# BoilerInterfaceV00.net
KiCad netlist of a schematic drawn in EAGLE
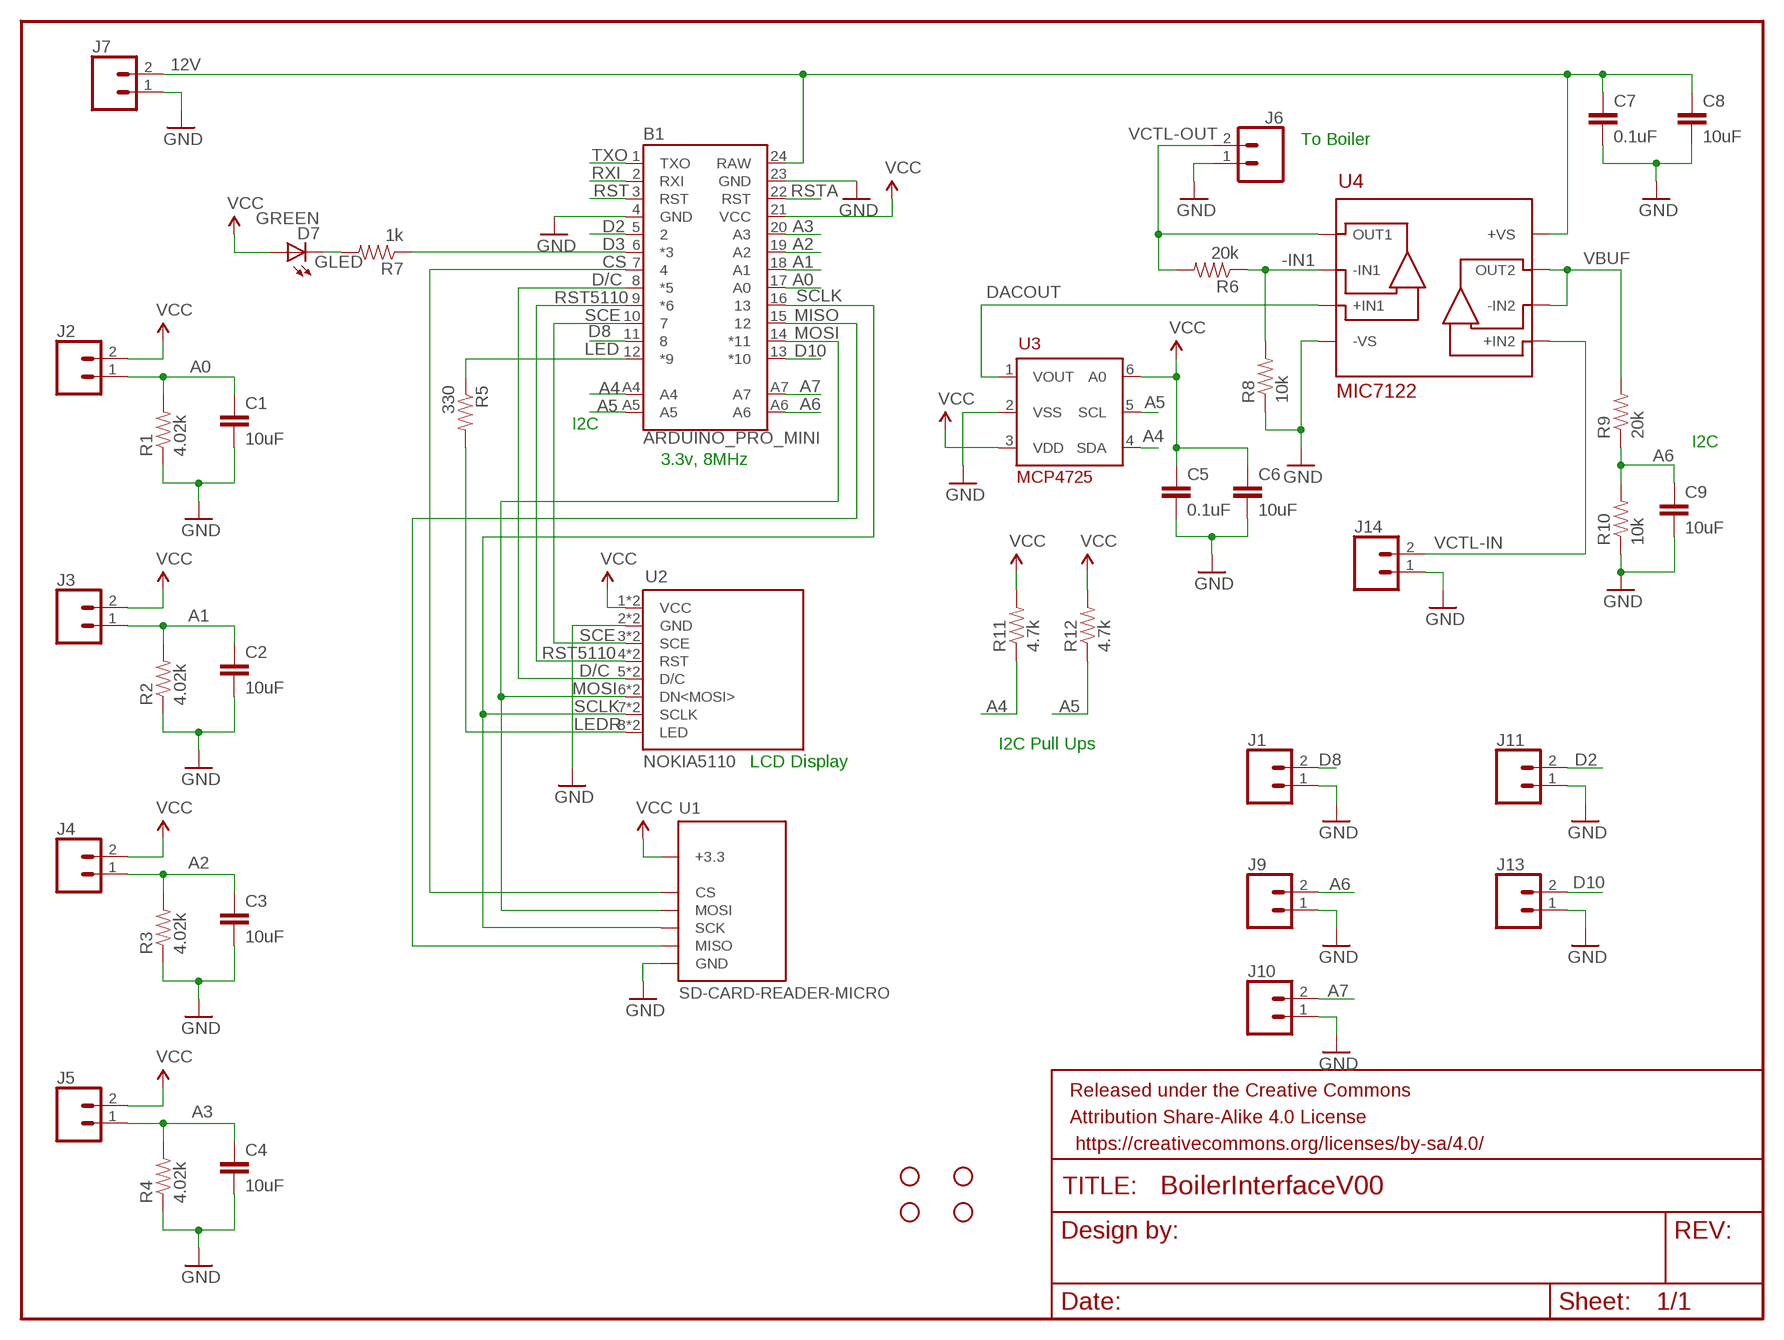
[diagram p0: schematic, sheet 1]

(export (version "E")
  (design (tool "Eeschema 10.0.6"))
  (components
    (comp (ref "B1")
      (value "ARDUINO_PRO_MINI")
      (footprint "eagle-import:ARDUINO_PRO_MINI")
      (libsource (lib "eagle-import") (part "ARDUINO_PRO_MINI"))
    )
    (comp (ref "C1")
      (value "10uF")
      (footprint "eagle-import:0805")
      (libsource (lib "eagle-import") (part "CAP0805"))
    )
    (comp (ref "C2")
      (value "10uF")
      (footprint "eagle-import:0805")
      (libsource (lib "eagle-import") (part "CAP0805"))
    )
    (comp (ref "C3")
      (value "10uF")
      (footprint "eagle-import:0805")
      (libsource (lib "eagle-import") (part "CAP0805"))
    )
    (comp (ref "C4")
      (value "10uF")
      (footprint "eagle-import:0805")
      (libsource (lib "eagle-import") (part "CAP0805"))
    )
    (comp (ref "C5")
      (value "0.1uF")
      (footprint "eagle-import:0805")
      (libsource (lib "eagle-import") (part "CAP0805"))
    )
    (comp (ref "C6")
      (value "10uF")
      (footprint "eagle-import:0805")
      (libsource (lib "eagle-import") (part "CAP0805"))
    )
    (comp (ref "C7")
      (value "0.1uF")
      (footprint "eagle-import:0805")
      (libsource (lib "eagle-import") (part "CAP0805"))
    )
    (comp (ref "C8")
      (value "10uF")
      (footprint "eagle-import:0805")
      (libsource (lib "eagle-import") (part "CAP0805"))
    )
    (comp (ref "C9")
      (value "10uF")
      (footprint "eagle-import:0805")
      (libsource (lib "eagle-import") (part "CAP0805"))
    )
    (comp (ref "D7")
      (value "GREEN")
      (footprint "eagle-import:LED-0603")
      (libsource (lib "eagle-import") (part "LED-GREEN0603"))
    )
    (comp (ref "FRAME1")
      (value "FRAME-LETTER")
      (footprint "eagle-import:CREATIVE_COMMONS")
      (libsource (lib "eagle-import") (part "FRAME-LETTER"))
    )
    (comp (ref "J1")
      (value "CONN_02")
      (footprint "eagle-import:1X02")
      (libsource (lib "eagle-import") (part "CONN_02"))
    )
    (comp (ref "J2")
      (value "CONN_025MM")
      (footprint "eagle-import:SCREWTERMINAL-5MM-2")
      (libsource (lib "eagle-import") (part "CONN_025MM"))
    )
    (comp (ref "J3")
      (value "CONN_025MM")
      (footprint "eagle-import:SCREWTERMINAL-5MM-2")
      (libsource (lib "eagle-import") (part "CONN_025MM"))
    )
    (comp (ref "J4")
      (value "CONN_025MM")
      (footprint "eagle-import:SCREWTERMINAL-5MM-2")
      (libsource (lib "eagle-import") (part "CONN_025MM"))
    )
    (comp (ref "J5")
      (value "CONN_025MM")
      (footprint "eagle-import:SCREWTERMINAL-5MM-2")
      (libsource (lib "eagle-import") (part "CONN_025MM"))
    )
    (comp (ref "J6")
      (value "CONN_025MM")
      (footprint "eagle-import:SCREWTERMINAL-5MM-2")
      (libsource (lib "eagle-import") (part "CONN_025MM"))
    )
    (comp (ref "J7")
      (value "CONN_025MM")
      (footprint "eagle-import:SCREWTERMINAL-5MM-2")
      (libsource (lib "eagle-import") (part "CONN_025MM"))
    )
    (comp (ref "J9")
      (value "CONN_02")
      (footprint "eagle-import:1X02")
      (libsource (lib "eagle-import") (part "CONN_02"))
    )
    (comp (ref "J10")
      (value "CONN_02")
      (footprint "eagle-import:1X02")
      (libsource (lib "eagle-import") (part "CONN_02"))
    )
    (comp (ref "J11")
      (value "CONN_02")
      (footprint "eagle-import:1X02")
      (libsource (lib "eagle-import") (part "CONN_02"))
    )
    (comp (ref "J13")
      (value "CONN_02")
      (footprint "eagle-import:1X02")
      (libsource (lib "eagle-import") (part "CONN_02"))
    )
    (comp (ref "J14")
      (value "CONN_025MM")
      (footprint "eagle-import:SCREWTERMINAL-5MM-2")
      (libsource (lib "eagle-import") (part "CONN_025MM"))
    )
    (comp (ref "R1")
      (value "4.02k")
      (footprint "eagle-import:0805")
      (libsource (lib "eagle-import") (part "RESISTOR0805-RES"))
    )
    (comp (ref "R2")
      (value "4.02k")
      (footprint "eagle-import:0805")
      (libsource (lib "eagle-import") (part "RESISTOR0805-RES"))
    )
    (comp (ref "R3")
      (value "4.02k")
      (footprint "eagle-import:0805")
      (libsource (lib "eagle-import") (part "RESISTOR0805-RES"))
    )
    (comp (ref "R4")
      (value "4.02k")
      (footprint "eagle-import:0805")
      (libsource (lib "eagle-import") (part "RESISTOR0805-RES"))
    )
    (comp (ref "R5")
      (value "330")
      (footprint "eagle-import:0603-RES")
      (libsource (lib "eagle-import") (part "RESISTOR0603"))
    )
    (comp (ref "R6")
      (value "20k")
      (footprint "eagle-import:0805")
      (libsource (lib "eagle-import") (part "RESISTOR0805-RES"))
    )
    (comp (ref "R7")
      (value "1k")
      (footprint "eagle-import:0805")
      (libsource (lib "eagle-import") (part "SparkFun-Resistors_RESISTOR0805-RES"))
    )
    (comp (ref "R8")
      (value "10k")
      (footprint "eagle-import:0805")
      (libsource (lib "eagle-import") (part "RESISTOR0805-RES"))
    )
    (comp (ref "R9")
      (value "20k")
      (footprint "eagle-import:0805")
      (libsource (lib "eagle-import") (part "RESISTOR0805-RES"))
    )
    (comp (ref "R10")
      (value "10k")
      (footprint "eagle-import:0805")
      (libsource (lib "eagle-import") (part "RESISTOR0805-RES"))
    )
    (comp (ref "R11")
      (value "4.7k")
      (footprint "eagle-import:0805")
      (libsource (lib "eagle-import") (part "RESISTOR0805-RES"))
    )
    (comp (ref "R12")
      (value "4.7k")
      (footprint "eagle-import:0805")
      (libsource (lib "eagle-import") (part "RESISTOR0805-RES"))
    )
    (comp (ref "STANDOFF1")
      (value "STAND-OFF")
      (footprint "eagle-import:STAND-OFF")
      (libsource (lib "eagle-import") (part "STAND-OFF"))
    )
    (comp (ref "STANDOFF2")
      (value "STAND-OFF")
      (footprint "eagle-import:STAND-OFF")
      (libsource (lib "eagle-import") (part "STAND-OFF"))
    )
    (comp (ref "STANDOFF3")
      (value "STAND-OFF")
      (footprint "eagle-import:STAND-OFF")
      (libsource (lib "eagle-import") (part "STAND-OFF"))
    )
    (comp (ref "STANDOFF4")
      (value "STAND-OFF")
      (footprint "eagle-import:STAND-OFF")
      (libsource (lib "eagle-import") (part "STAND-OFF"))
    )
    (comp (ref "U1")
      (value "SD-CARD-READER-MICRO")
      (footprint "eagle-import:MICROSD_MOLEX")
      (libsource (lib "eagle-import") (part "SD-CARD-READER-MICRO"))
    )
    (comp (ref "U2")
      (value "NOKIA5110")
      (footprint "eagle-import:NOKIA5110")
      (libsource (lib "eagle-import") (part "NOKIA5110"))
    )
    (comp (ref "U3")
      (value "MCP4725")
      (footprint "eagle-import:SOT23-6L")
      (libsource (lib "eagle-import") (part "MCP4725"))
    )
    (comp (ref "U4")
      (value "MIC7122")
      (footprint "eagle-import:MSOP8")
      (libsource (lib "eagle-import") (part "MIC7122"))
    )
  )
  (nets
    (net (code "1") (name "/-IN1") (class "Default")
      (node (ref "R6") (pin "1") (pinfunction "1_1") (pintype "passive"))
      (node (ref "R8") (pin "2") (pinfunction "2_2") (pintype "passive"))
      (node (ref "U4") (pin "2") (pinfunction "-IN1_2") (pintype "bidirectional"))
    )
    (net (code "2") (name "/12V") (class "Default")
      (node (ref "B1") (pin "24") (pinfunction "RAW_24") (pintype "power_in"))
      (node (ref "C7") (pin "1") (pinfunction "1_1") (pintype "passive"))
      (node (ref "C8") (pin "1") (pinfunction "1_1") (pintype "passive"))
      (node (ref "J7") (pin "2") (pinfunction "2_2") (pintype "passive"))
      (node (ref "U4") (pin "8") (pinfunction "+VS_8") (pintype "bidirectional"))
    )
    (net (code "3") (name "/A0") (class "Default")
      (node (ref "B1") (pin "17") (pinfunction "A0_17") (pintype "bidirectional"))
      (node (ref "C1") (pin "1") (pinfunction "1_1") (pintype "passive"))
      (node (ref "J2") (pin "1") (pinfunction "1_1") (pintype "passive"))
      (node (ref "R1") (pin "2") (pinfunction "2_2") (pintype "passive"))
    )
    (net (code "4") (name "/A1") (class "Default")
      (node (ref "B1") (pin "18") (pinfunction "A1_18") (pintype "bidirectional"))
      (node (ref "C2") (pin "1") (pinfunction "1_1") (pintype "passive"))
      (node (ref "J3") (pin "1") (pinfunction "1_1") (pintype "passive"))
      (node (ref "R2") (pin "2") (pinfunction "2_2") (pintype "passive"))
    )
    (net (code "5") (name "/A2") (class "Default")
      (node (ref "B1") (pin "19") (pinfunction "A2_19") (pintype "bidirectional"))
      (node (ref "C3") (pin "1") (pinfunction "1_1") (pintype "passive"))
      (node (ref "J4") (pin "1") (pinfunction "1_1") (pintype "passive"))
      (node (ref "R3") (pin "2") (pinfunction "2_2") (pintype "passive"))
    )
    (net (code "6") (name "/A3") (class "Default")
      (node (ref "B1") (pin "20") (pinfunction "A3_20") (pintype "bidirectional"))
      (node (ref "C4") (pin "1") (pinfunction "1_1") (pintype "passive"))
      (node (ref "J5") (pin "1") (pinfunction "1_1") (pintype "passive"))
      (node (ref "R4") (pin "2") (pinfunction "2_2") (pintype "passive"))
    )
    (net (code "7") (name "/A4") (class "Default")
      (node (ref "B1") (pin "A4") (pinfunction "A4_A4") (pintype "bidirectional"))
      (node (ref "R11") (pin "1") (pinfunction "1_1") (pintype "passive"))
      (node (ref "U3") (pin "4") (pinfunction "SDA_4") (pintype "bidirectional"))
    )
    (net (code "8") (name "/A5") (class "Default")
      (node (ref "B1") (pin "A5") (pinfunction "A5_A5") (pintype "bidirectional"))
      (node (ref "R12") (pin "1") (pinfunction "1_1") (pintype "passive"))
      (node (ref "U3") (pin "5") (pinfunction "SCL_5") (pintype "bidirectional"))
    )
    (net (code "9") (name "/A6") (class "Default")
      (node (ref "B1") (pin "A6") (pinfunction "A6_A6") (pintype "bidirectional"))
      (node (ref "C9") (pin "1") (pinfunction "1_1") (pintype "passive"))
      (node (ref "J9") (pin "2") (pinfunction "2_2") (pintype "passive"))
      (node (ref "R10") (pin "2") (pinfunction "2_2") (pintype "passive"))
      (node (ref "R9") (pin "1") (pinfunction "1_1") (pintype "passive"))
    )
    (net (code "10") (name "/A7") (class "Default")
      (node (ref "B1") (pin "A7") (pinfunction "A7_A7") (pintype "bidirectional"))
      (node (ref "J10") (pin "2") (pinfunction "2_2") (pintype "passive"))
    )
    (net (code "11") (name "/CS") (class "Default")
      (node (ref "B1") (pin "7") (pinfunction "4_7") (pintype "bidirectional"))
      (node (ref "U1") (pin "P$2") (pinfunction "CS_P$2") (pintype "bidirectional"))
    )
    (net (code "12") (name "/D2") (class "Default")
      (node (ref "B1") (pin "5") (pinfunction "2_5") (pintype "bidirectional"))
      (node (ref "J11") (pin "2") (pinfunction "2_2") (pintype "passive"))
    )
    (net (code "13") (name "/D3") (class "Default")
      (node (ref "B1") (pin "6") (pinfunction "*3_6") (pintype "bidirectional"))
      (node (ref "R7") (pin "1") (pinfunction "1_1") (pintype "passive"))
    )
    (net (code "14") (name "/D8") (class "Default")
      (node (ref "B1") (pin "11") (pinfunction "8_11") (pintype "bidirectional"))
      (node (ref "J1") (pin "2") (pinfunction "2_2") (pintype "passive"))
    )
    (net (code "15") (name "/D10") (class "Default")
      (node (ref "B1") (pin "13") (pinfunction "*10_13") (pintype "bidirectional"))
      (node (ref "J13") (pin "2") (pinfunction "2_2") (pintype "passive"))
    )
    (net (code "16") (name "/DACOUT") (class "Default")
      (node (ref "U3") (pin "1") (pinfunction "VOUT_1") (pintype "bidirectional"))
      (node (ref "U4") (pin "3") (pinfunction "+IN1_3") (pintype "bidirectional"))
    )
    (net (code "17") (name "/D{slash}C") (class "Default")
      (node (ref "B1") (pin "8") (pinfunction "*5_8") (pintype "bidirectional"))
      (node (ref "U2") (pin "13") (pinfunction "D/C_13") (pintype "bidirectional"))
      (node (ref "U2") (pin "5") (pinfunction "D/C_5") (pintype "bidirectional"))
    )
    (net (code "18") (name "/GLED") (class "Default")
      (node (ref "D7") (pin "C") (pinfunction "C_C") (pintype "passive"))
      (node (ref "R7") (pin "2") (pinfunction "2_2") (pintype "passive"))
    )
    (net (code "19") (name "/LED") (class "Default")
      (node (ref "B1") (pin "12") (pinfunction "*9_12") (pintype "bidirectional"))
      (node (ref "R5") (pin "1") (pinfunction "1_1") (pintype "passive"))
    )
    (net (code "20") (name "/LEDR") (class "Default")
      (node (ref "R5") (pin "2") (pinfunction "2_2") (pintype "passive"))
      (node (ref "U2") (pin "16") (pinfunction "LED_16") (pintype "bidirectional"))
      (node (ref "U2") (pin "8") (pinfunction "LED_8") (pintype "bidirectional"))
    )
    (net (code "21") (name "/MISO") (class "Default")
      (node (ref "B1") (pin "15") (pinfunction "12_15") (pintype "bidirectional"))
      (node (ref "U1") (pin "P$7") (pinfunction "MISO_P$7") (pintype "bidirectional"))
    )
    (net (code "22") (name "/MOSI") (class "Default")
      (node (ref "B1") (pin "14") (pinfunction "*11_14") (pintype "bidirectional"))
      (node (ref "U1") (pin "P$3") (pinfunction "MOSI_P$3") (pintype "bidirectional"))
      (node (ref "U2") (pin "14") (pinfunction "DN<MOSI>_14") (pintype "bidirectional"))
      (node (ref "U2") (pin "6") (pinfunction "DN<MOSI>_6") (pintype "bidirectional"))
    )
    (net (code "23") (name "/RST") (class "Default")
      (node (ref "B1") (pin "3") (pinfunction "RST_3") (pintype "bidirectional"))
    )
    (net (code "24") (name "/RST5110") (class "Default")
      (node (ref "B1") (pin "9") (pinfunction "*6_9") (pintype "bidirectional"))
      (node (ref "U2") (pin "12") (pinfunction "RST_12") (pintype "bidirectional"))
      (node (ref "U2") (pin "4") (pinfunction "RST_4") (pintype "bidirectional"))
    )
    (net (code "25") (name "/RSTA") (class "Default")
      (node (ref "B1") (pin "22") (pinfunction "RST_22") (pintype "bidirectional"))
    )
    (net (code "26") (name "/RXI") (class "Default")
      (node (ref "B1") (pin "2") (pinfunction "RXI_2") (pintype "bidirectional"))
    )
    (net (code "27") (name "/SCE") (class "Default")
      (node (ref "B1") (pin "10") (pinfunction "7_10") (pintype "bidirectional"))
      (node (ref "U2") (pin "11") (pinfunction "SCE_11") (pintype "bidirectional"))
      (node (ref "U2") (pin "3") (pinfunction "SCE_3") (pintype "bidirectional"))
    )
    (net (code "28") (name "/SCLK") (class "Default")
      (node (ref "B1") (pin "16") (pinfunction "13_16") (pintype "bidirectional"))
      (node (ref "U1") (pin "P$5") (pinfunction "SCK_P$5") (pintype "bidirectional"))
      (node (ref "U2") (pin "15") (pinfunction "SCLK_15") (pintype "bidirectional"))
      (node (ref "U2") (pin "7") (pinfunction "SCLK_7") (pintype "bidirectional"))
    )
    (net (code "29") (name "/TXO") (class "Default")
      (node (ref "B1") (pin "1") (pinfunction "TXO_1") (pintype "bidirectional"))
    )
    (net (code "30") (name "/VBUF") (class "Default")
      (node (ref "R9") (pin "2") (pinfunction "2_2") (pintype "passive"))
      (node (ref "U4") (pin "6") (pinfunction "-IN2_6") (pintype "bidirectional"))
      (node (ref "U4") (pin "7") (pinfunction "OUT2_7") (pintype "bidirectional"))
    )
    (net (code "31") (name "/VCTL-IN") (class "Default")
      (node (ref "J14") (pin "2") (pinfunction "2_2") (pintype "passive"))
      (node (ref "U4") (pin "5") (pinfunction "+IN2_5") (pintype "bidirectional"))
    )
    (net (code "32") (name "/VCTL-OUT") (class "Default")
      (node (ref "J6") (pin "2") (pinfunction "2_2") (pintype "passive"))
      (node (ref "R6") (pin "2") (pinfunction "2_2") (pintype "passive"))
      (node (ref "U4") (pin "1") (pinfunction "OUT1_1") (pintype "bidirectional"))
    )
    (net (code "33") (name "GND") (class "Default")
      (node (ref "B1") (pin "23") (pinfunction "GND_23") (pintype "power_in"))
      (node (ref "B1") (pin "4") (pinfunction "GND_4") (pintype "power_in"))
      (node (ref "C1") (pin "2") (pinfunction "2_2") (pintype "passive"))
      (node (ref "C2") (pin "2") (pinfunction "2_2") (pintype "passive"))
      (node (ref "C3") (pin "2") (pinfunction "2_2") (pintype "passive"))
      (node (ref "C4") (pin "2") (pinfunction "2_2") (pintype "passive"))
      (node (ref "C5") (pin "2") (pinfunction "2_2") (pintype "passive"))
      (node (ref "C6") (pin "2") (pinfunction "2_2") (pintype "passive"))
      (node (ref "C7") (pin "2") (pinfunction "2_2") (pintype "passive"))
      (node (ref "C8") (pin "2") (pinfunction "2_2") (pintype "passive"))
      (node (ref "C9") (pin "2") (pinfunction "2_2") (pintype "passive"))
      (node (ref "J1") (pin "1") (pinfunction "1_1") (pintype "passive"))
      (node (ref "J10") (pin "1") (pinfunction "1_1") (pintype "passive"))
      (node (ref "J11") (pin "1") (pinfunction "1_1") (pintype "passive"))
      (node (ref "J13") (pin "1") (pinfunction "1_1") (pintype "passive"))
      (node (ref "J14") (pin "1") (pinfunction "1_1") (pintype "passive"))
      (node (ref "J6") (pin "1") (pinfunction "1_1") (pintype "passive"))
      (node (ref "J7") (pin "1") (pinfunction "1_1") (pintype "passive"))
      (node (ref "J9") (pin "1") (pinfunction "1_1") (pintype "passive"))
      (node (ref "R1") (pin "1") (pinfunction "1_1") (pintype "passive"))
      (node (ref "R10") (pin "1") (pinfunction "1_1") (pintype "passive"))
      (node (ref "R2") (pin "1") (pinfunction "1_1") (pintype "passive"))
      (node (ref "R3") (pin "1") (pinfunction "1_1") (pintype "passive"))
      (node (ref "R4") (pin "1") (pinfunction "1_1") (pintype "passive"))
      (node (ref "R8") (pin "1") (pinfunction "1_1") (pintype "passive"))
      (node (ref "U1") (pin "P$10") (pinfunction "GND_P$10") (pintype "bidirectional"))
      (node (ref "U1") (pin "P$11") (pinfunction "GND_P$11") (pintype "bidirectional"))
      (node (ref "U1") (pin "P$12") (pinfunction "GND_P$12") (pintype "bidirectional"))
      (node (ref "U1") (pin "P$6") (pinfunction "GND_P$6") (pintype "bidirectional"))
      (node (ref "U1") (pin "P$9") (pinfunction "GND_P$9") (pintype "bidirectional"))
      (node (ref "U2") (pin "10") (pinfunction "GND_10") (pintype "bidirectional"))
      (node (ref "U2") (pin "2") (pinfunction "GND_2") (pintype "bidirectional"))
      (node (ref "U3") (pin "2") (pinfunction "VSS_2") (pintype "bidirectional"))
      (node (ref "U4") (pin "4") (pinfunction "-VS_4") (pintype "bidirectional"))
    )
    (net (code "34") (name "VCC") (class "Default")
      (node (ref "B1") (pin "21") (pinfunction "VCC_21") (pintype "power_in"))
      (node (ref "C5") (pin "1") (pinfunction "1_1") (pintype "passive"))
      (node (ref "C6") (pin "1") (pinfunction "1_1") (pintype "passive"))
      (node (ref "D7") (pin "A") (pinfunction "A_A") (pintype "passive"))
      (node (ref "J2") (pin "2") (pinfunction "2_2") (pintype "passive"))
      (node (ref "J3") (pin "2") (pinfunction "2_2") (pintype "passive"))
      (node (ref "J4") (pin "2") (pinfunction "2_2") (pintype "passive"))
      (node (ref "J5") (pin "2") (pinfunction "2_2") (pintype "passive"))
      (node (ref "R11") (pin "2") (pinfunction "2_2") (pintype "passive"))
      (node (ref "R12") (pin "2") (pinfunction "2_2") (pintype "passive"))
      (node (ref "U1") (pin "P$4") (pinfunction "+3.3_P$4") (pintype "bidirectional"))
      (node (ref "U2") (pin "1") (pinfunction "VCC_1") (pintype "bidirectional"))
      (node (ref "U2") (pin "9") (pinfunction "VCC_9") (pintype "bidirectional"))
      (node (ref "U3") (pin "3") (pinfunction "VDD_3") (pintype "bidirectional"))
      (node (ref "U3") (pin "6") (pinfunction "A0_6") (pintype "bidirectional"))
    )
  )
)
